# Follower.net
KiCad netlist of a schematic drawn in EAGLE
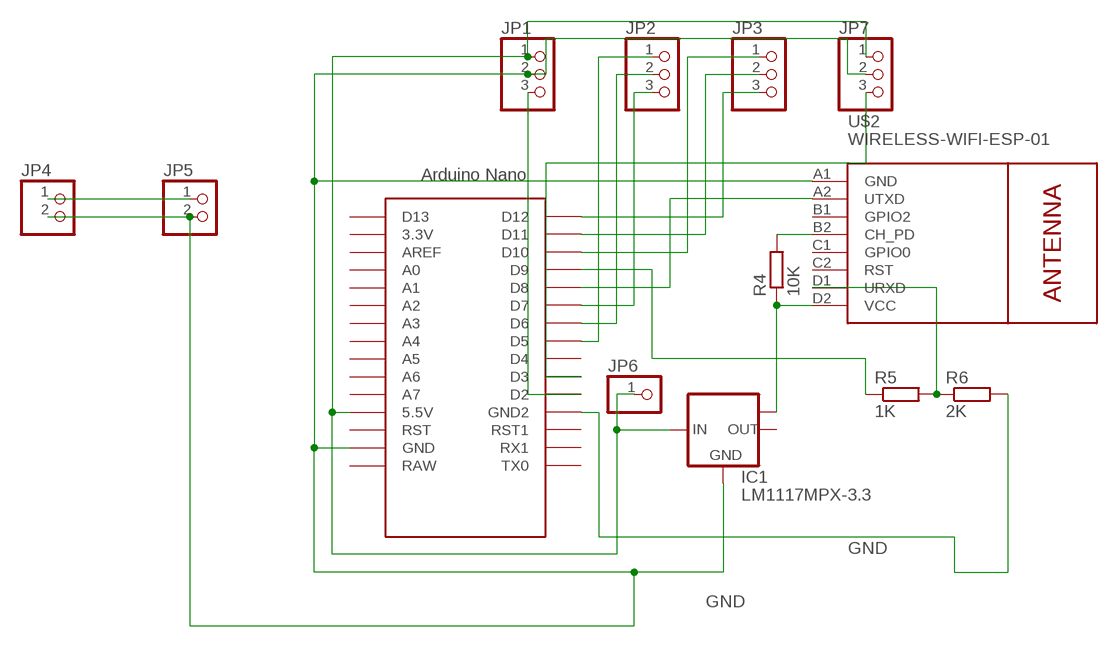
[diagram p0: schematic, sheet 1]

(export (version "E")
  (design (tool "Eeschema 10.0.6"))
  (components
    (comp (ref "IC1")
      (value "LM1117MPX-3.3")
      (footprint "eagle-import:SOT223")
      (libsource (lib "eagle-import") (part "LM1117MPX-3.3"))
    )
    (comp (ref "JP1")
      (value "PINHD-1X3")
      (footprint "eagle-import:1X03")
      (libsource (lib "eagle-import") (part "PINHD-1X3"))
    )
    (comp (ref "JP2")
      (value "PINHD-1X3")
      (footprint "eagle-import:1X03")
      (libsource (lib "eagle-import") (part "PINHD-1X3"))
    )
    (comp (ref "JP3")
      (value "PINHD-1X3")
      (footprint "eagle-import:1X03")
      (libsource (lib "eagle-import") (part "PINHD-1X3"))
    )
    (comp (ref "JP4")
      (value "PINHD-1X2")
      (footprint "eagle-import:1X02")
      (libsource (lib "eagle-import") (part "PINHD-1X2"))
    )
    (comp (ref "JP5")
      (value "PINHD-1X2")
      (footprint "eagle-import:1X02")
      (libsource (lib "eagle-import") (part "PINHD-1X2"))
    )
    (comp (ref "JP6")
      (value "PINHD-1X1")
      (footprint "eagle-import:1X01")
      (libsource (lib "eagle-import") (part "PINHD-1X1"))
    )
    (comp (ref "JP7")
      (value "PINHD-1X3")
      (footprint "eagle-import:1X03")
      (libsource (lib "eagle-import") (part "PINHD-1X3"))
    )
    (comp (ref "R4")
      (value "10K")
      (footprint "eagle-import:0207_10")
      (libsource (lib "eagle-import") (part "R-EU_0207/10"))
    )
    (comp (ref "R5")
      (value "1K")
      (footprint "eagle-import:0207_10")
      (libsource (lib "eagle-import") (part "R-EU_0207/10"))
    )
    (comp (ref "R6")
      (value "2K")
      (footprint "eagle-import:0207_10")
      (libsource (lib "eagle-import") (part "R-EU_0207/10"))
    )
    (comp (ref "U$1")
      (value "NANO")
      (footprint "eagle-import:NANO")
      (libsource (lib "eagle-import") (part "NANO"))
    )
    (comp (ref "U$2")
      (value "WIRELESS-WIFI-ESP-01")
      (footprint "eagle-import:WIRELESS-WIFI-ESP-01")
      (libsource (lib "eagle-import") (part "WIRELESS-WIFI-ESP-01"))
    )
  )
  (nets
    (net (code "1") (name "/GND") (class "Default")
      (node (ref "IC1") (pin "1") (pinfunction "GND_1") (pintype "input"))
      (node (ref "JP1") (pin "2") (pinfunction "2_2") (pintype "passive"))
      (node (ref "JP4") (pin "2") (pinfunction "2_2") (pintype "passive"))
      (node (ref "JP5") (pin "2") (pinfunction "2_2") (pintype "passive"))
      (node (ref "JP7") (pin "2") (pinfunction "2_2") (pintype "passive"))
      (node (ref "R6") (pin "2") (pinfunction "2_2") (pintype "passive"))
      (node (ref "U$1") (pin "GND") (pinfunction "GND_GND") (pintype "bidirectional"))
      (node (ref "U$1") (pin "GND1") (pinfunction "GND2_GND1") (pintype "bidirectional"))
      (node (ref "U$2") (pin "A1") (pinfunction "GND_A1") (pintype "power_in"))
    )
    (net (code "2") (name "Net-(IC1-IN)") (class "Default")
      (node (ref "IC1") (pin "3") (pinfunction "IN_3") (pintype "input"))
      (node (ref "JP1") (pin "1") (pinfunction "1_1") (pintype "passive"))
      (node (ref "JP6") (pin "1") (pinfunction "1_1") (pintype "passive"))
      (node (ref "JP7") (pin "1") (pinfunction "1_1") (pintype "passive"))
      (node (ref "U$1") (pin "5V") (pinfunction "5.5V_5V") (pintype "bidirectional"))
    )
    (net (code "3") (name "Net-(IC1-OUT1)") (class "Default")
      (node (ref "IC1") (pin "TAB") (pinfunction "OUT1_TAB") (pintype "passive"))
      (node (ref "R4") (pin "1") (pinfunction "1_1") (pintype "passive"))
      (node (ref "U$2") (pin "D2") (pinfunction "VCC_D2") (pintype "power_in"))
    )
    (net (code "4") (name "Net-(JP1-Pad3)") (class "Default")
      (node (ref "JP1") (pin "3") (pinfunction "3_3") (pintype "passive"))
      (node (ref "U$1") (pin "D2") (pinfunction "D2_D2") (pintype "bidirectional"))
    )
    (net (code "5") (name "Net-(JP2-Pad1)") (class "Default")
      (node (ref "JP2") (pin "1") (pinfunction "1_1") (pintype "passive"))
      (node (ref "U$1") (pin "D5") (pinfunction "D5_D5") (pintype "bidirectional"))
    )
    (net (code "6") (name "Net-(JP2-Pad2)") (class "Default")
      (node (ref "JP2") (pin "2") (pinfunction "2_2") (pintype "passive"))
      (node (ref "U$1") (pin "D6") (pinfunction "D6_D6") (pintype "bidirectional"))
    )
    (net (code "7") (name "Net-(JP2-Pad3)") (class "Default")
      (node (ref "JP2") (pin "3") (pinfunction "3_3") (pintype "passive"))
      (node (ref "U$1") (pin "D7") (pinfunction "D7_D7") (pintype "bidirectional"))
    )
    (net (code "8") (name "Net-(JP3-Pad1)") (class "Default")
      (node (ref "JP3") (pin "1") (pinfunction "1_1") (pintype "passive"))
      (node (ref "U$1") (pin "D10") (pinfunction "D10_D10") (pintype "bidirectional"))
    )
    (net (code "9") (name "Net-(JP3-Pad2)") (class "Default")
      (node (ref "JP3") (pin "2") (pinfunction "2_2") (pintype "passive"))
      (node (ref "U$1") (pin "D11") (pinfunction "D11_D11") (pintype "bidirectional"))
    )
    (net (code "10") (name "Net-(JP3-Pad3)") (class "Default")
      (node (ref "JP3") (pin "3") (pinfunction "3_3") (pintype "passive"))
      (node (ref "U$1") (pin "D12") (pinfunction "D12_D12") (pintype "bidirectional"))
    )
    (net (code "11") (name "Net-(JP4-Pad1)") (class "Default")
      (node (ref "JP4") (pin "1") (pinfunction "1_1") (pintype "passive"))
      (node (ref "JP5") (pin "1") (pinfunction "1_1") (pintype "passive"))
    )
    (net (code "12") (name "Net-(JP7-Pad3)") (class "Default")
      (node (ref "JP7") (pin "3") (pinfunction "3_3") (pintype "passive"))
      (node (ref "U$1") (pin "D3") (pinfunction "D3_D3") (pintype "bidirectional"))
    )
    (net (code "13") (name "Net-(R5-Pad1)") (class "Default")
      (node (ref "R5") (pin "1") (pinfunction "1_1") (pintype "passive"))
      (node (ref "U$1") (pin "D9") (pinfunction "D9_D9") (pintype "bidirectional"))
    )
    (net (code "14") (name "Net-(U$2-CH_PD)") (class "Default")
      (node (ref "R4") (pin "2") (pinfunction "2_2") (pintype "passive"))
      (node (ref "U$2") (pin "B2") (pinfunction "CH_PD_B2") (pintype "bidirectional"))
    )
    (net (code "15") (name "Net-(U$2-URXD)") (class "Default")
      (node (ref "R5") (pin "2") (pinfunction "2_2") (pintype "passive"))
      (node (ref "R6") (pin "1") (pinfunction "1_1") (pintype "passive"))
      (node (ref "U$2") (pin "D1") (pinfunction "URXD_D1") (pintype "bidirectional"))
    )
    (net (code "16") (name "Net-(U$2-UTXD)") (class "Default")
      (node (ref "U$1") (pin "D8") (pinfunction "D8_D8") (pintype "bidirectional"))
      (node (ref "U$2") (pin "A2") (pinfunction "UTXD_A2") (pintype "bidirectional"))
    )
    (net (code "17") (name "unconnected-(IC1-OUT-Pad2)") (class "Default")
      (node (ref "IC1") (pin "2") (pinfunction "OUT_2") (pintype "passive"))
    )
    (net (code "18") (name "unconnected-(U$1-Pad3.3V)") (class "Default")
      (node (ref "U$1") (pin "3.3V") (pinfunction "3.3V_3.3V") (pintype "bidirectional"))
    )
    (net (code "19") (name "unconnected-(U$1-PadA0)") (class "Default")
      (node (ref "U$1") (pin "A0") (pinfunction "A0_A0") (pintype "bidirectional"))
    )
    (net (code "20") (name "unconnected-(U$1-PadA1)") (class "Default")
      (node (ref "U$1") (pin "A1") (pinfunction "A1_A1") (pintype "bidirectional"))
    )
    (net (code "21") (name "unconnected-(U$1-PadA2)") (class "Default")
      (node (ref "U$1") (pin "A2") (pinfunction "A2_A2") (pintype "bidirectional"))
    )
    (net (code "22") (name "unconnected-(U$1-PadA3)") (class "Default")
      (node (ref "U$1") (pin "A3") (pinfunction "A3_A3") (pintype "bidirectional"))
    )
    (net (code "23") (name "unconnected-(U$1-PadA4)") (class "Default")
      (node (ref "U$1") (pin "A4") (pinfunction "A4_A4") (pintype "bidirectional"))
    )
    (net (code "24") (name "unconnected-(U$1-PadA5)") (class "Default")
      (node (ref "U$1") (pin "A5") (pinfunction "A5_A5") (pintype "bidirectional"))
    )
    (net (code "25") (name "unconnected-(U$1-PadA6)") (class "Default")
      (node (ref "U$1") (pin "A6") (pinfunction "A6_A6") (pintype "bidirectional"))
    )
    (net (code "26") (name "unconnected-(U$1-PadA7)") (class "Default")
      (node (ref "U$1") (pin "A7") (pinfunction "A7_A7") (pintype "bidirectional"))
    )
    (net (code "27") (name "unconnected-(U$1-PadAREF)") (class "Default")
      (node (ref "U$1") (pin "AREF") (pinfunction "AREF_AREF") (pintype "bidirectional"))
    )
    (net (code "28") (name "unconnected-(U$1-PadD4)") (class "Default")
      (node (ref "U$1") (pin "D4") (pinfunction "D4_D4") (pintype "bidirectional"))
    )
    (net (code "29") (name "unconnected-(U$1-PadD13)") (class "Default")
      (node (ref "U$1") (pin "D13") (pinfunction "D13_D13") (pintype "bidirectional"))
    )
    (net (code "30") (name "unconnected-(U$1-PadICSP1)") (class "Default")
      (node (ref "U$1") (pin "ICSP1") (pinfunction "ICSP1_ICSP1") (pintype "bidirectional"))
    )
    (net (code "31") (name "unconnected-(U$1-PadICSP2)") (class "Default")
      (node (ref "U$1") (pin "ICSP2") (pinfunction "ICSP2_ICSP2") (pintype "bidirectional"))
    )
    (net (code "32") (name "unconnected-(U$1-PadICSP3)") (class "Default")
      (node (ref "U$1") (pin "ICSP3") (pinfunction "ICSP3_ICSP3") (pintype "bidirectional"))
    )
    (net (code "33") (name "unconnected-(U$1-PadICSP4)") (class "Default")
      (node (ref "U$1") (pin "ICSP4") (pinfunction "ICSP4_ICSP4") (pintype "bidirectional"))
    )
    (net (code "34") (name "unconnected-(U$1-PadICSP5)") (class "Default")
      (node (ref "U$1") (pin "ICSP5") (pinfunction "ICSP5_ICSP5") (pintype "bidirectional"))
    )
    (net (code "35") (name "unconnected-(U$1-PadICSP6)") (class "Default")
      (node (ref "U$1") (pin "ICSP6") (pinfunction "ICSP6_ICSP6") (pintype "bidirectional"))
    )
    (net (code "36") (name "unconnected-(U$1-PadRAW)") (class "Default")
      (node (ref "U$1") (pin "RAW") (pinfunction "RAW_RAW") (pintype "bidirectional"))
    )
    (net (code "37") (name "unconnected-(U$1-PadRST)") (class "Default")
      (node (ref "U$1") (pin "RST") (pinfunction "RST_RST") (pintype "bidirectional"))
    )
    (net (code "38") (name "unconnected-(U$1-PadRST1)") (class "Default")
      (node (ref "U$1") (pin "RST1") (pinfunction "RST1_RST1") (pintype "bidirectional"))
    )
    (net (code "39") (name "unconnected-(U$1-PadRX1)") (class "Default")
      (node (ref "U$1") (pin "RX1") (pinfunction "RX1_RX1") (pintype "bidirectional"))
    )
    (net (code "40") (name "unconnected-(U$1-PadTX0)") (class "Default")
      (node (ref "U$1") (pin "TX0") (pinfunction "TX0_TX0") (pintype "bidirectional"))
    )
    (net (code "41") (name "unconnected-(U$2-GPIO0-PadC1)") (class "Default")
      (node (ref "U$2") (pin "C1") (pinfunction "GPIO0_C1") (pintype "bidirectional"))
    )
    (net (code "42") (name "unconnected-(U$2-GPIO2-PadB1)") (class "Default")
      (node (ref "U$2") (pin "B1") (pinfunction "GPIO2_B1") (pintype "bidirectional"))
    )
    (net (code "43") (name "unconnected-(U$2-RST-PadC2)") (class "Default")
      (node (ref "U$2") (pin "C2") (pinfunction "RST_C2") (pintype "bidirectional"))
    )
  )
)
